# Camera_shield_v1.net
KiCad netlist of a schematic drawn in EAGLE
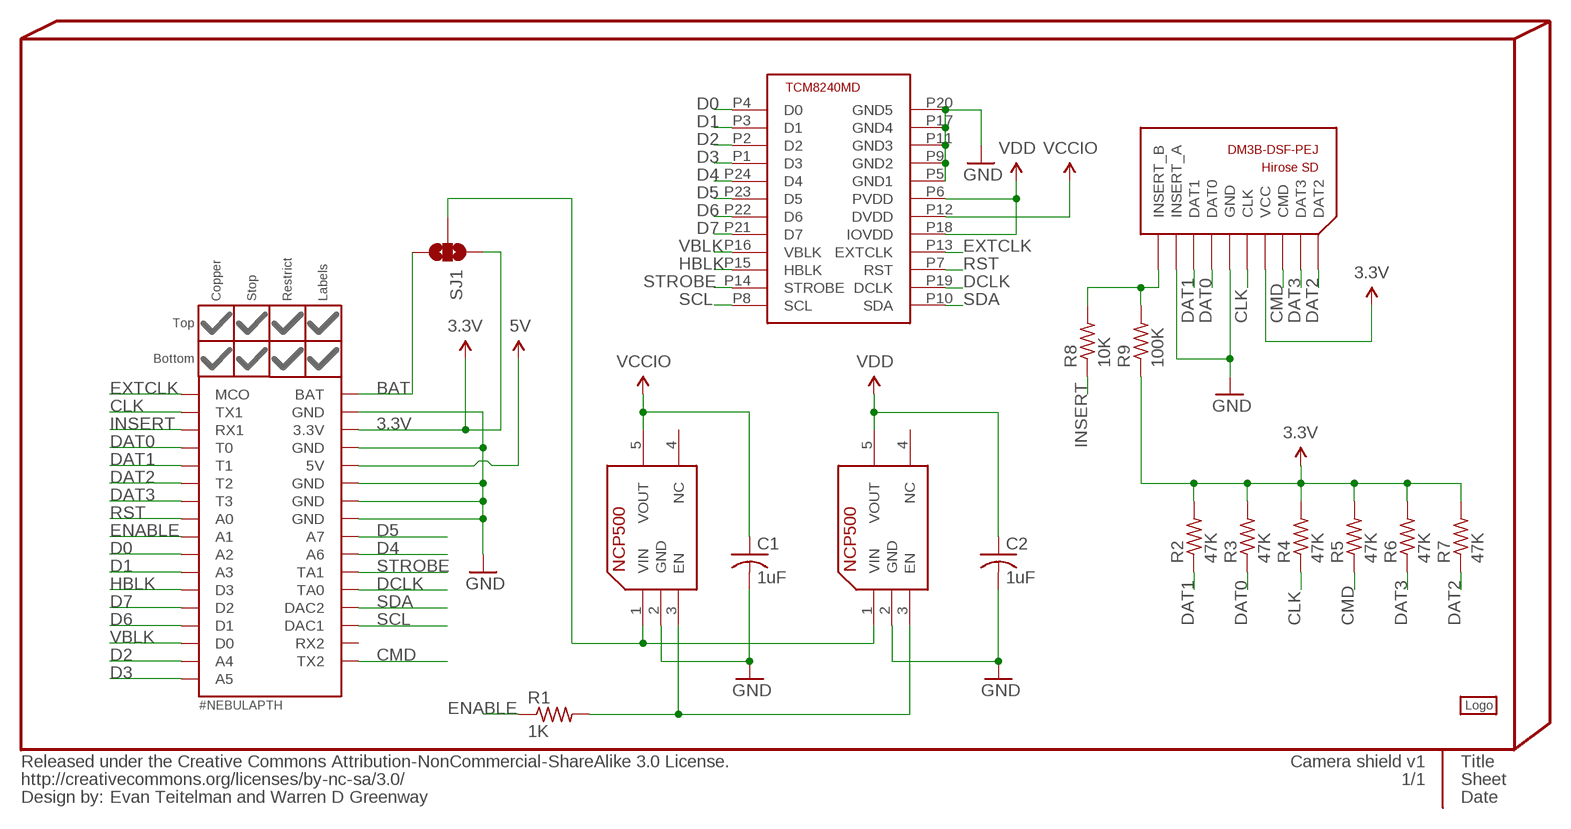
[diagram p0: schematic, sheet 1]

(export (version "E")
  (design (tool "Eeschema 10.0.6"))
  (components
    (comp (ref "C1")
      (value "1uF")
      (footprint "eagle-import:C0402")
      (libsource (lib "eagle-import") (part "C-USC0402"))
    )
    (comp (ref "C2")
      (value "1uF")
      (footprint "eagle-import:C0402")
      (libsource (lib "eagle-import") (part "C-USC0402"))
    )
    (comp (ref "INFO2")
      (value "Evan Teitelman and Warren D Greenway")
      (footprint "eagle-import:%CC-NC-SA")
      (libsource (lib "eagle-import") (part "%CC-NC-SA"))
    )
    (comp (ref "LOGO1")
      (value "#PYGMYLOGONORMAL")
      (footprint "eagle-import:#PYGMYLOGO")
      (libsource (lib "eagle-import") (part "#PYGMYLOGOLARGE"))
    )
    (comp (ref "NEBULA1")
      (value "#NEBULAPTH")
      (footprint "eagle-import:#NEBULA-PTH")
      (libsource (lib "eagle-import") (part "#NEBULAPTH"))
    )
    (comp (ref "R1")
      (value "1K")
      (footprint "eagle-import:R0402")
      (libsource (lib "eagle-import") (part "R-US_R0402"))
    )
    (comp (ref "R2")
      (value "47K")
      (footprint "eagle-import:R0402")
      (libsource (lib "eagle-import") (part "R-US_R0402"))
    )
    (comp (ref "R3")
      (value "47K")
      (footprint "eagle-import:R0402")
      (libsource (lib "eagle-import") (part "R-US_R0402"))
    )
    (comp (ref "R4")
      (value "47K")
      (footprint "eagle-import:R0402")
      (libsource (lib "eagle-import") (part "R-US_R0402"))
    )
    (comp (ref "R5")
      (value "47K")
      (footprint "eagle-import:R0402")
      (libsource (lib "eagle-import") (part "R-US_R0402"))
    )
    (comp (ref "R6")
      (value "47K")
      (footprint "eagle-import:R0402")
      (libsource (lib "eagle-import") (part "R-US_R0402"))
    )
    (comp (ref "R7")
      (value "47K")
      (footprint "eagle-import:R0402")
      (libsource (lib "eagle-import") (part "R-US_R0402"))
    )
    (comp (ref "R8")
      (value "10K")
      (footprint "eagle-import:R0402")
      (libsource (lib "eagle-import") (part "R-US_R0402"))
    )
    (comp (ref "R9")
      (value "100K")
      (footprint "eagle-import:R0402")
      (libsource (lib "eagle-import") (part "R-US_R0402"))
    )
    (comp (ref "SJ1")
      (value "SOLDERJUMPER_2WAYS")
      (footprint "eagle-import:SJ_3")
      (libsource (lib "eagle-import") (part "SOLDERJUMPER_2WAYS"))
    )
    (comp (ref "U$2")
      (value "TCM8240MD")
      (footprint "eagle-import:TCM8240MD")
      (libsource (lib "eagle-import") (part "TCM8240MD"))
    )
    (comp (ref "U$3")
      (value "NCP500")
      (footprint "eagle-import:SOT23-5L")
      (libsource (lib "eagle-import") (part "NCP500"))
    )
    (comp (ref "U$4")
      (value "NCP500")
      (footprint "eagle-import:SOT23-5L")
      (libsource (lib "eagle-import") (part "NCP500"))
    )
    (comp (ref "U$5")
      (value "HIROSE-SDCARD-DM3B-DSF-PEJ")
      (footprint "eagle-import:HIROSE-SDCARD-DM3B-DSF-PEJ")
      (libsource (lib "eagle-import") (part "HIROSE-SDCARD-DM3B-DSF-PEJ"))
    )
  )
  (nets
    (net (code "1") (name "/BAT") (class "Default")
      (node (ref "NEBULA1") (pin "BAT") (pinfunction "BAT_BAT") (pintype "bidirectional"))
      (node (ref "SJ1") (pin "3") (pinfunction "3_3") (pintype "passive"))
    )
    (net (code "2") (name "/CLK") (class "Default")
      (node (ref "NEBULA1") (pin "COM1_TX") (pinfunction "TX1_COM1_TX") (pintype "bidirectional"))
      (node (ref "R4") (pin "1") (pinfunction "1_1") (pintype "passive"))
      (node (ref "U$5") (pin "P$5") (pinfunction "CLK_P$5") (pintype "bidirectional"))
    )
    (net (code "3") (name "/CMD") (class "Default")
      (node (ref "NEBULA1") (pin "COM2_TX") (pinfunction "TX2_COM2_TX") (pintype "bidirectional"))
      (node (ref "R5") (pin "1") (pinfunction "1_1") (pintype "passive"))
      (node (ref "U$5") (pin "P$3") (pinfunction "CMD_P$3") (pintype "bidirectional"))
    )
    (net (code "4") (name "/D0") (class "Default")
      (node (ref "NEBULA1") (pin "A2") (pinfunction "A2_A2") (pintype "bidirectional"))
      (node (ref "U$2") (pin "P4") (pinfunction "D0_P4") (pintype "bidirectional"))
    )
    (net (code "5") (name "/D1") (class "Default")
      (node (ref "NEBULA1") (pin "A3") (pinfunction "A3_A3") (pintype "bidirectional"))
      (node (ref "U$2") (pin "P3") (pinfunction "D1_P3") (pintype "bidirectional"))
    )
    (net (code "6") (name "/D2") (class "Default")
      (node (ref "NEBULA1") (pin "A4") (pinfunction "A4_A4") (pintype "bidirectional"))
      (node (ref "U$2") (pin "P2") (pinfunction "D2_P2") (pintype "bidirectional"))
    )
    (net (code "7") (name "/D3") (class "Default")
      (node (ref "NEBULA1") (pin "A5") (pinfunction "A5_A5") (pintype "bidirectional"))
      (node (ref "U$2") (pin "P1") (pinfunction "D3_P1") (pintype "bidirectional"))
    )
    (net (code "8") (name "/D4") (class "Default")
      (node (ref "NEBULA1") (pin "A6") (pinfunction "A6_A6") (pintype "bidirectional"))
      (node (ref "U$2") (pin "P24") (pinfunction "D4_P24") (pintype "bidirectional"))
    )
    (net (code "9") (name "/D5") (class "Default")
      (node (ref "NEBULA1") (pin "A7") (pinfunction "A7_A7") (pintype "bidirectional"))
      (node (ref "U$2") (pin "P23") (pinfunction "D5_P23") (pintype "bidirectional"))
    )
    (net (code "10") (name "/D6") (class "Default")
      (node (ref "NEBULA1") (pin "D1") (pinfunction "D1_D1") (pintype "bidirectional"))
      (node (ref "U$2") (pin "P22") (pinfunction "D6_P22") (pintype "bidirectional"))
    )
    (net (code "11") (name "/D7") (class "Default")
      (node (ref "NEBULA1") (pin "D2") (pinfunction "D2_D2") (pintype "bidirectional"))
      (node (ref "U$2") (pin "P21") (pinfunction "D7_P21") (pintype "bidirectional"))
    )
    (net (code "12") (name "/DAT0") (class "Default")
      (node (ref "NEBULA1") (pin "T0") (pinfunction "T0_T0") (pintype "bidirectional"))
      (node (ref "R3") (pin "1") (pinfunction "1_1") (pintype "passive"))
      (node (ref "U$5") (pin "P$7") (pinfunction "DAT0_P$7") (pintype "bidirectional"))
    )
    (net (code "13") (name "/DAT1") (class "Default")
      (node (ref "NEBULA1") (pin "T1") (pinfunction "T1_T1") (pintype "bidirectional"))
      (node (ref "R2") (pin "1") (pinfunction "1_1") (pintype "passive"))
      (node (ref "U$5") (pin "P$8") (pinfunction "DAT1_P$8") (pintype "bidirectional"))
    )
    (net (code "14") (name "/DAT2") (class "Default")
      (node (ref "NEBULA1") (pin "T2") (pinfunction "T2_T2") (pintype "bidirectional"))
      (node (ref "R7") (pin "1") (pinfunction "1_1") (pintype "passive"))
      (node (ref "U$5") (pin "P$1") (pinfunction "DAT2_P$1") (pintype "bidirectional"))
    )
    (net (code "15") (name "/DAT3") (class "Default")
      (node (ref "NEBULA1") (pin "T3") (pinfunction "T3_T3") (pintype "bidirectional"))
      (node (ref "R6") (pin "1") (pinfunction "1_1") (pintype "passive"))
      (node (ref "U$5") (pin "P$2") (pinfunction "DAT3_P$2") (pintype "bidirectional"))
    )
    (net (code "16") (name "/DCLK") (class "Default")
      (node (ref "NEBULA1") (pin "TA0") (pinfunction "TA0_TA0") (pintype "bidirectional"))
      (node (ref "U$2") (pin "P19") (pinfunction "DCLK_P19") (pintype "bidirectional"))
    )
    (net (code "17") (name "/ENABLE") (class "Default")
      (node (ref "NEBULA1") (pin "A1") (pinfunction "A1_A1") (pintype "bidirectional"))
      (node (ref "R1") (pin "1") (pinfunction "1_1") (pintype "passive"))
    )
    (net (code "18") (name "/EXTCLK") (class "Default")
      (node (ref "NEBULA1") (pin "MCO") (pinfunction "MCO_MCO") (pintype "bidirectional"))
      (node (ref "U$2") (pin "P13") (pinfunction "EXTCLK_P13") (pintype "bidirectional"))
    )
    (net (code "19") (name "/HBLK") (class "Default")
      (node (ref "NEBULA1") (pin "D3") (pinfunction "D3_D3") (pintype "bidirectional"))
      (node (ref "U$2") (pin "P15") (pinfunction "HBLK_P15") (pintype "bidirectional"))
    )
    (net (code "20") (name "/INSERT") (class "Default")
      (node (ref "NEBULA1") (pin "COM1_RX") (pinfunction "RX1_COM1_RX") (pintype "bidirectional"))
      (node (ref "R8") (pin "1") (pinfunction "1_1") (pintype "passive"))
    )
    (net (code "21") (name "/RST") (class "Default")
      (node (ref "NEBULA1") (pin "A0") (pinfunction "A0_A0") (pintype "bidirectional"))
      (node (ref "U$2") (pin "P7") (pinfunction "RST_P7") (pintype "bidirectional"))
    )
    (net (code "22") (name "/SCL") (class "Default")
      (node (ref "NEBULA1") (pin "DAC1") (pinfunction "DAC1_DAC1") (pintype "bidirectional"))
      (node (ref "U$2") (pin "P8") (pinfunction "SCL_P8") (pintype "bidirectional"))
    )
    (net (code "23") (name "/SDA") (class "Default")
      (node (ref "NEBULA1") (pin "DAC2") (pinfunction "DAC2_DAC2") (pintype "bidirectional"))
      (node (ref "U$2") (pin "P10") (pinfunction "SDA_P10") (pintype "bidirectional"))
    )
    (net (code "24") (name "/STROBE") (class "Default")
      (node (ref "NEBULA1") (pin "TA1") (pinfunction "TA1_TA1") (pintype "bidirectional"))
      (node (ref "U$2") (pin "P14") (pinfunction "STROBE_P14") (pintype "bidirectional"))
    )
    (net (code "25") (name "/VBLK") (class "Default")
      (node (ref "NEBULA1") (pin "D0") (pinfunction "D0_D0") (pintype "bidirectional"))
      (node (ref "U$2") (pin "P16") (pinfunction "VBLK_P16") (pintype "bidirectional"))
    )
    (net (code "26") (name "@3.3V") (class "Default")
      (node (ref "NEBULA1") (pin "3.3V") (pinfunction "3.3V_3.3V") (pintype "bidirectional"))
      (node (ref "R2") (pin "2") (pinfunction "2_2") (pintype "passive"))
      (node (ref "R3") (pin "2") (pinfunction "2_2") (pintype "passive"))
      (node (ref "R4") (pin "2") (pinfunction "2_2") (pintype "passive"))
      (node (ref "R5") (pin "2") (pinfunction "2_2") (pintype "passive"))
      (node (ref "R6") (pin "2") (pinfunction "2_2") (pintype "passive"))
      (node (ref "R7") (pin "2") (pinfunction "2_2") (pintype "passive"))
      (node (ref "R9") (pin "1") (pinfunction "1_1") (pintype "passive"))
      (node (ref "SJ1") (pin "1") (pinfunction "1_1") (pintype "passive"))
      (node (ref "U$5") (pin "P$4") (pinfunction "VCC_P$4") (pintype "bidirectional"))
    )
    (net (code "27") (name "@5V") (class "Default")
      (node (ref "NEBULA1") (pin "5V") (pinfunction "5V_5V") (pintype "bidirectional"))
    )
    (net (code "28") (name "@GND") (class "Default")
      (node (ref "C1") (pin "2") (pinfunction "2_2") (pintype "passive"))
      (node (ref "C2") (pin "2") (pinfunction "2_2") (pintype "passive"))
      (node (ref "NEBULA1") (pin "GND1") (pinfunction "GND_GND1") (pintype "bidirectional"))
      (node (ref "NEBULA1") (pin "GND2") (pinfunction "GND_GND2") (pintype "bidirectional"))
      (node (ref "NEBULA1") (pin "GND3") (pinfunction "GND_GND3") (pintype "bidirectional"))
      (node (ref "NEBULA1") (pin "GND4") (pinfunction "GND_GND4") (pintype "bidirectional"))
      (node (ref "NEBULA1") (pin "GND5") (pinfunction "GND_GND5") (pintype "bidirectional"))
      (node (ref "U$2") (pin "P11") (pinfunction "GND3_P11") (pintype "bidirectional"))
      (node (ref "U$2") (pin "P17") (pinfunction "GND4_P17") (pintype "bidirectional"))
      (node (ref "U$2") (pin "P20") (pinfunction "GND5_P20") (pintype "bidirectional"))
      (node (ref "U$2") (pin "P5") (pinfunction "GND1_P5") (pintype "bidirectional"))
      (node (ref "U$2") (pin "P9") (pinfunction "GND2_P9") (pintype "bidirectional"))
      (node (ref "U$3") (pin "2") (pinfunction "GND_2") (pintype "bidirectional"))
      (node (ref "U$4") (pin "2") (pinfunction "GND_2") (pintype "bidirectional"))
      (node (ref "U$5") (pin "P$6") (pinfunction "GND_P$6") (pintype "bidirectional"))
      (node (ref "U$5") (pin "P$9") (pinfunction "INSERT_A_P$9") (pintype "bidirectional"))
    )
    (net (code "29") (name "@VCCIO") (class "Default")
      (node (ref "C1") (pin "1") (pinfunction "1_1") (pintype "passive"))
      (node (ref "U$2") (pin "P12") (pinfunction "DVDD_P12") (pintype "bidirectional"))
      (node (ref "U$3") (pin "5") (pinfunction "VOUT_5") (pintype "bidirectional"))
    )
    (net (code "30") (name "@VDD") (class "Default")
      (node (ref "C2") (pin "1") (pinfunction "1_1") (pintype "passive"))
      (node (ref "U$2") (pin "P18") (pinfunction "IOVDD_P18") (pintype "bidirectional"))
      (node (ref "U$2") (pin "P6") (pinfunction "PVDD_P6") (pintype "bidirectional"))
      (node (ref "U$4") (pin "5") (pinfunction "VOUT_5") (pintype "bidirectional"))
    )
    (net (code "31") (name "Net-(U$3-EN)") (class "Default")
      (node (ref "R1") (pin "2") (pinfunction "2_2") (pintype "passive"))
      (node (ref "U$3") (pin "3") (pinfunction "EN_3") (pintype "bidirectional"))
      (node (ref "U$4") (pin "3") (pinfunction "EN_3") (pintype "bidirectional"))
    )
    (net (code "32") (name "Net-(U$3-VIN)") (class "Default")
      (node (ref "SJ1") (pin "2") (pinfunction "2_2") (pintype "passive"))
      (node (ref "U$3") (pin "1") (pinfunction "VIN_1") (pintype "bidirectional"))
      (node (ref "U$4") (pin "1") (pinfunction "VIN_1") (pintype "bidirectional"))
    )
    (net (code "33") (name "Net-(U$5A-INSERT_B)") (class "Default")
      (node (ref "R8") (pin "2") (pinfunction "2_2") (pintype "passive"))
      (node (ref "R9") (pin "2") (pinfunction "2_2") (pintype "passive"))
      (node (ref "U$5") (pin "P$11") (pinfunction "INSERT_B_P$11") (pintype "bidirectional"))
    )
    (net (code "34") (name "unconnected-(NEBULA1-RX2-PadCOM2_RX)") (class "Default")
      (node (ref "NEBULA1") (pin "COM2_RX") (pinfunction "RX2_COM2_RX") (pintype "bidirectional"))
    )
    (net (code "35") (name "unconnected-(U$3-NC-Pad4)") (class "Default")
      (node (ref "U$3") (pin "4") (pinfunction "NC_4") (pintype "bidirectional"))
    )
    (net (code "36") (name "unconnected-(U$4-NC-Pad4)") (class "Default")
      (node (ref "U$4") (pin "4") (pinfunction "NC_4") (pintype "bidirectional"))
    )
  )
)
